# UnknownSchematic.net
KiCad netlist of a schematic drawn in EAGLE
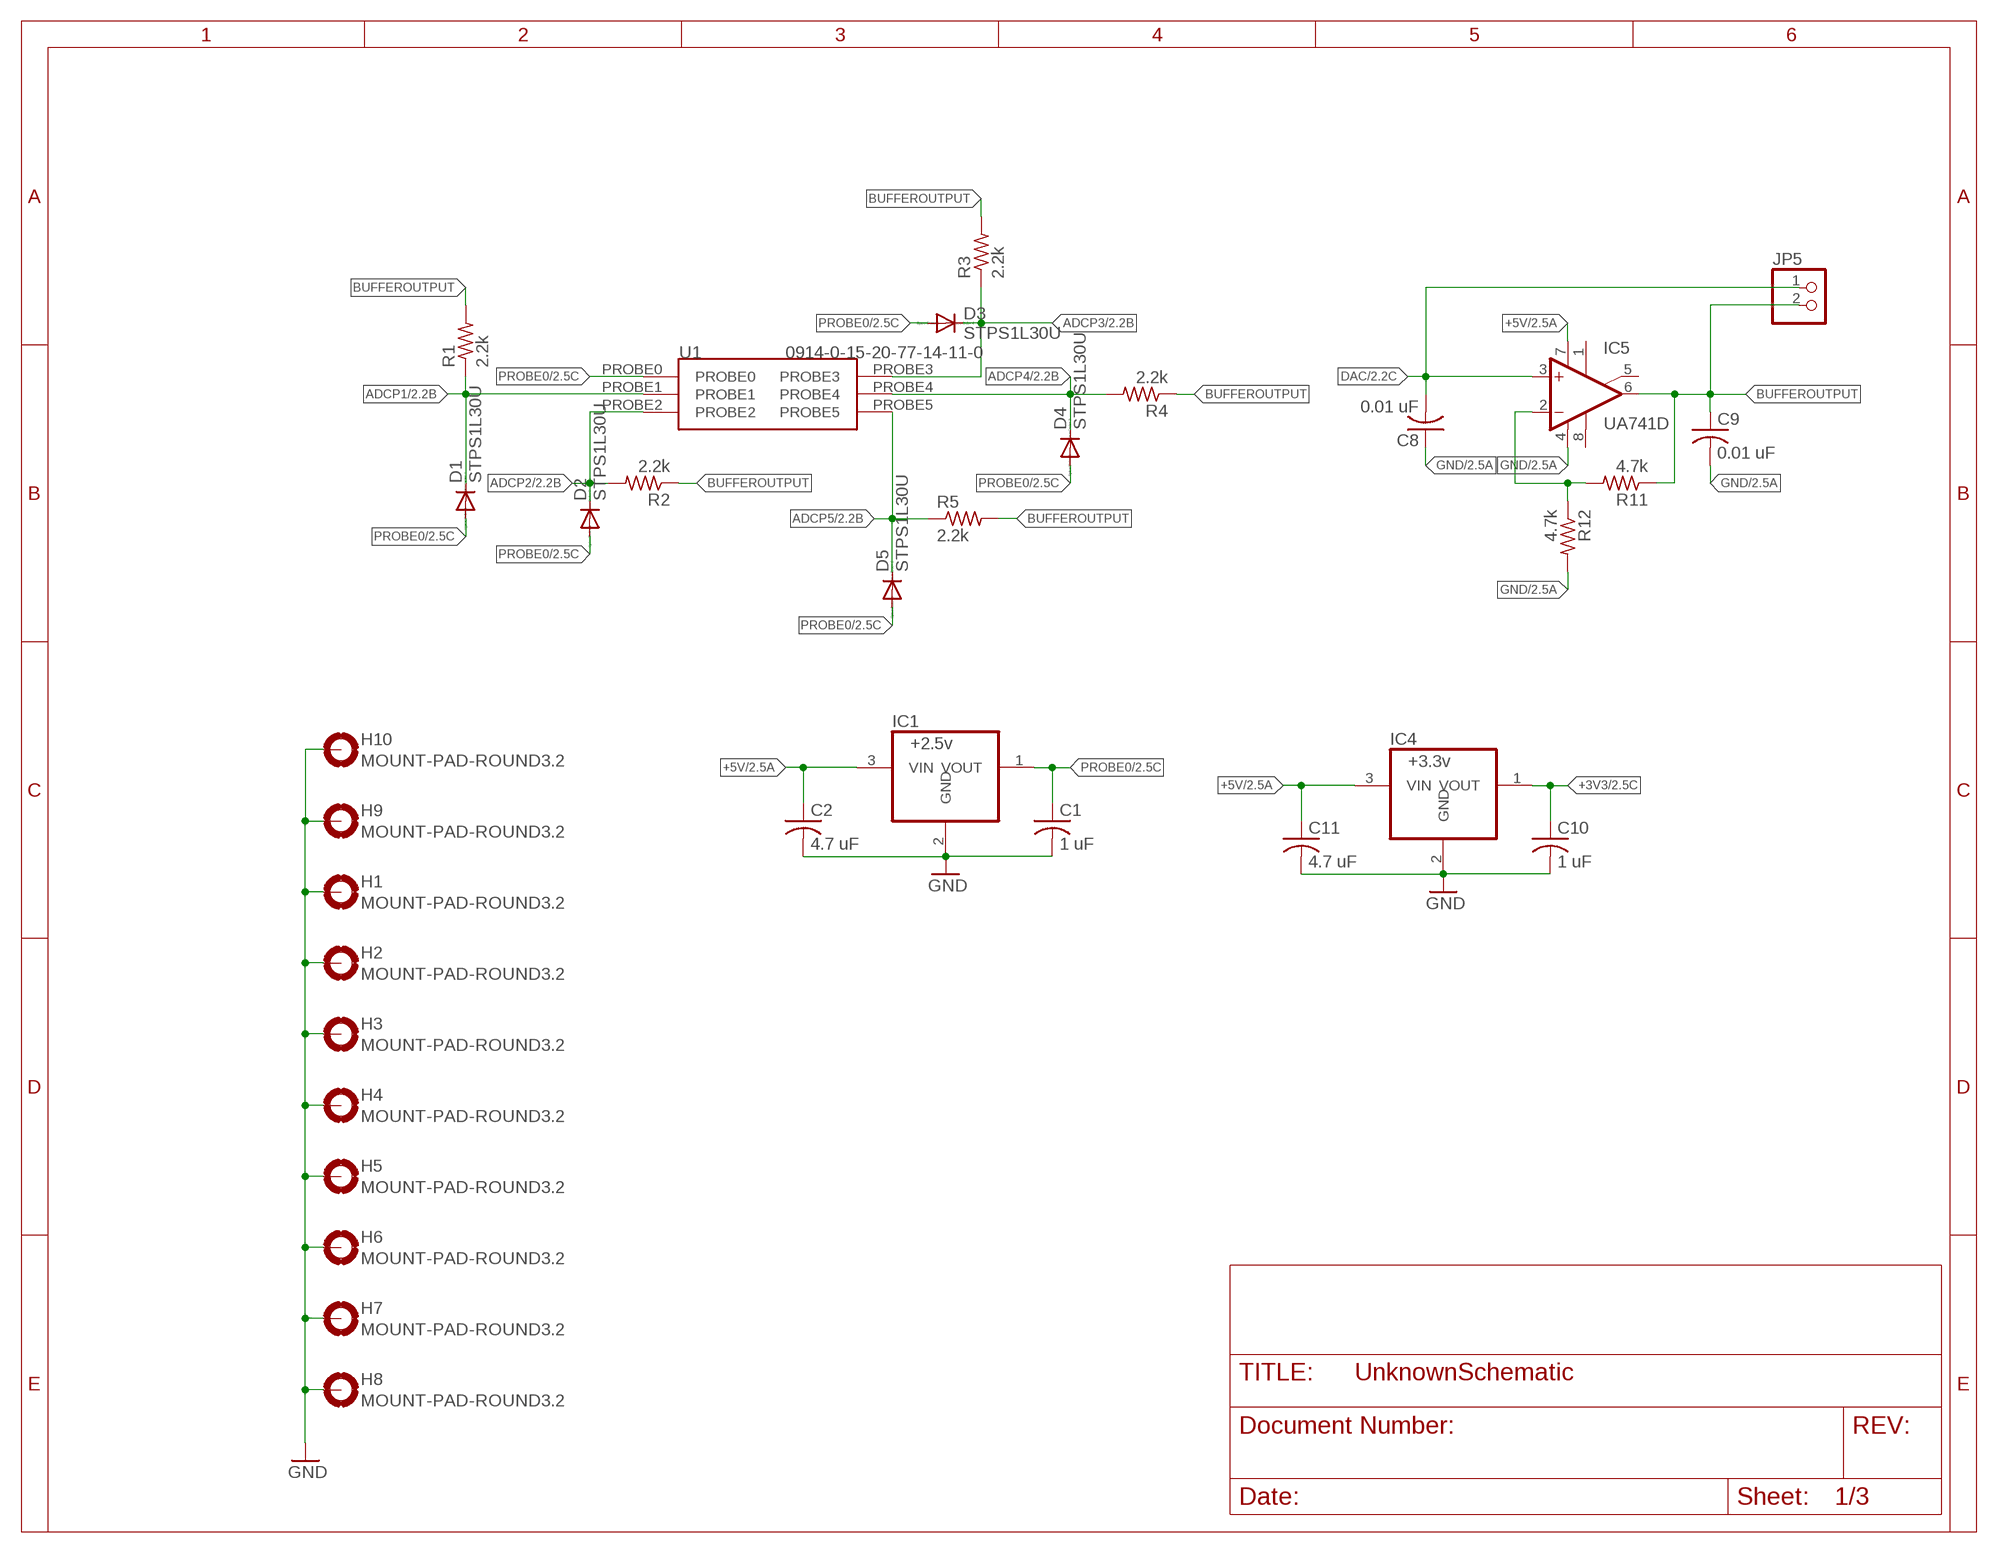
[diagram p0: schematic, sheet 1]
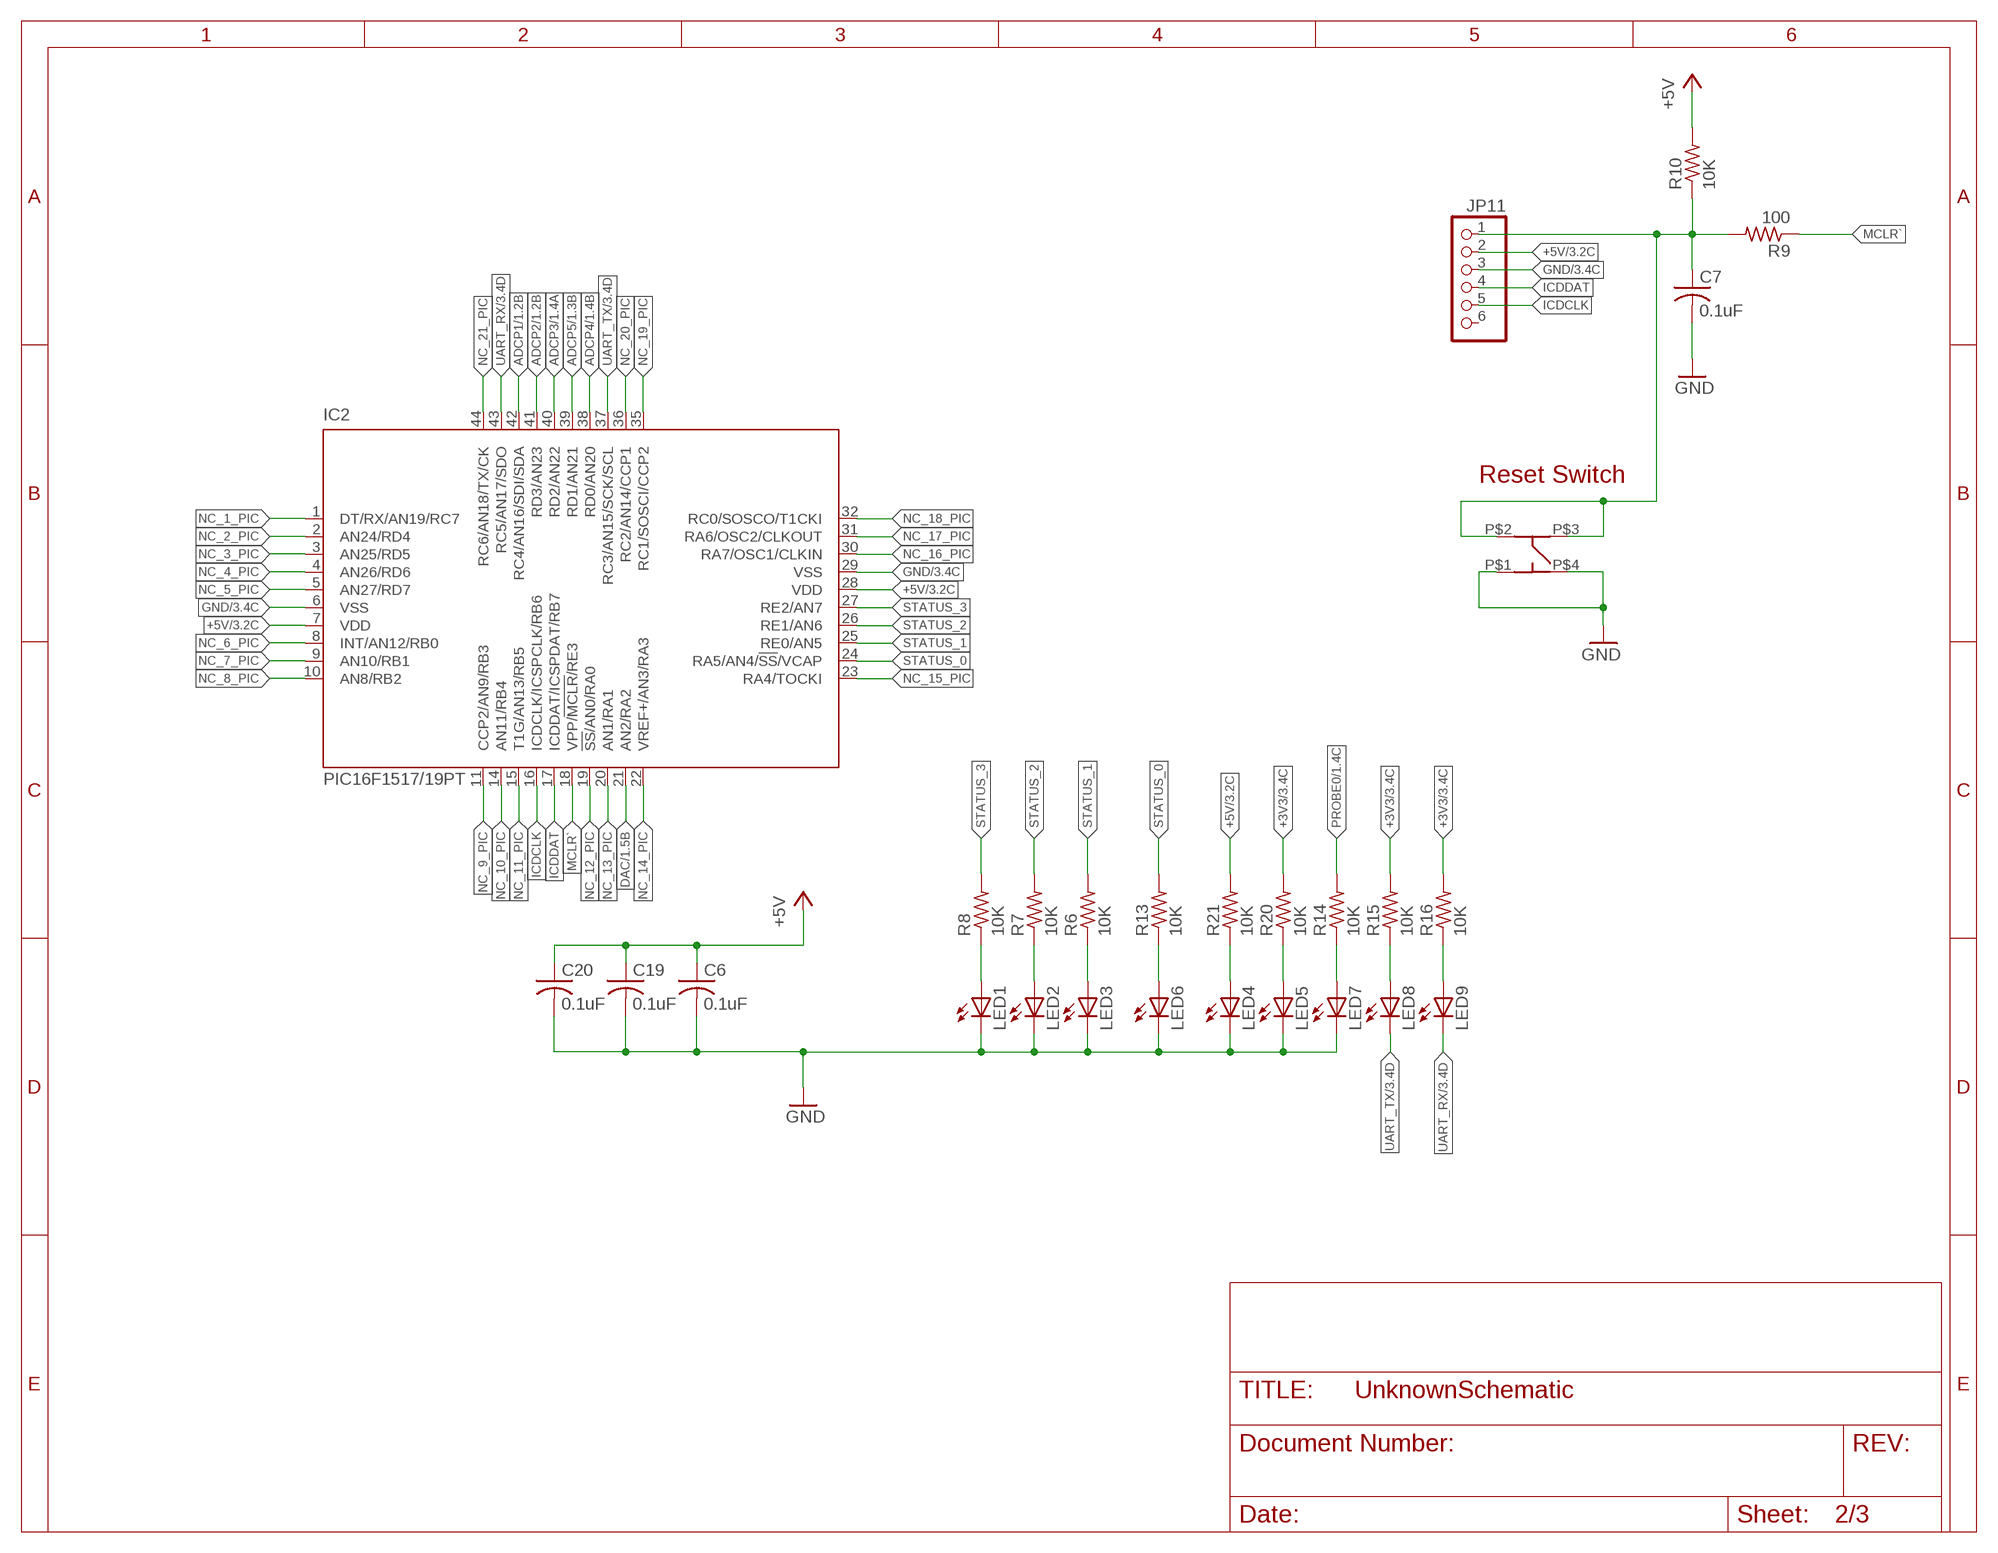
[diagram p1: schematic, sheet 2]
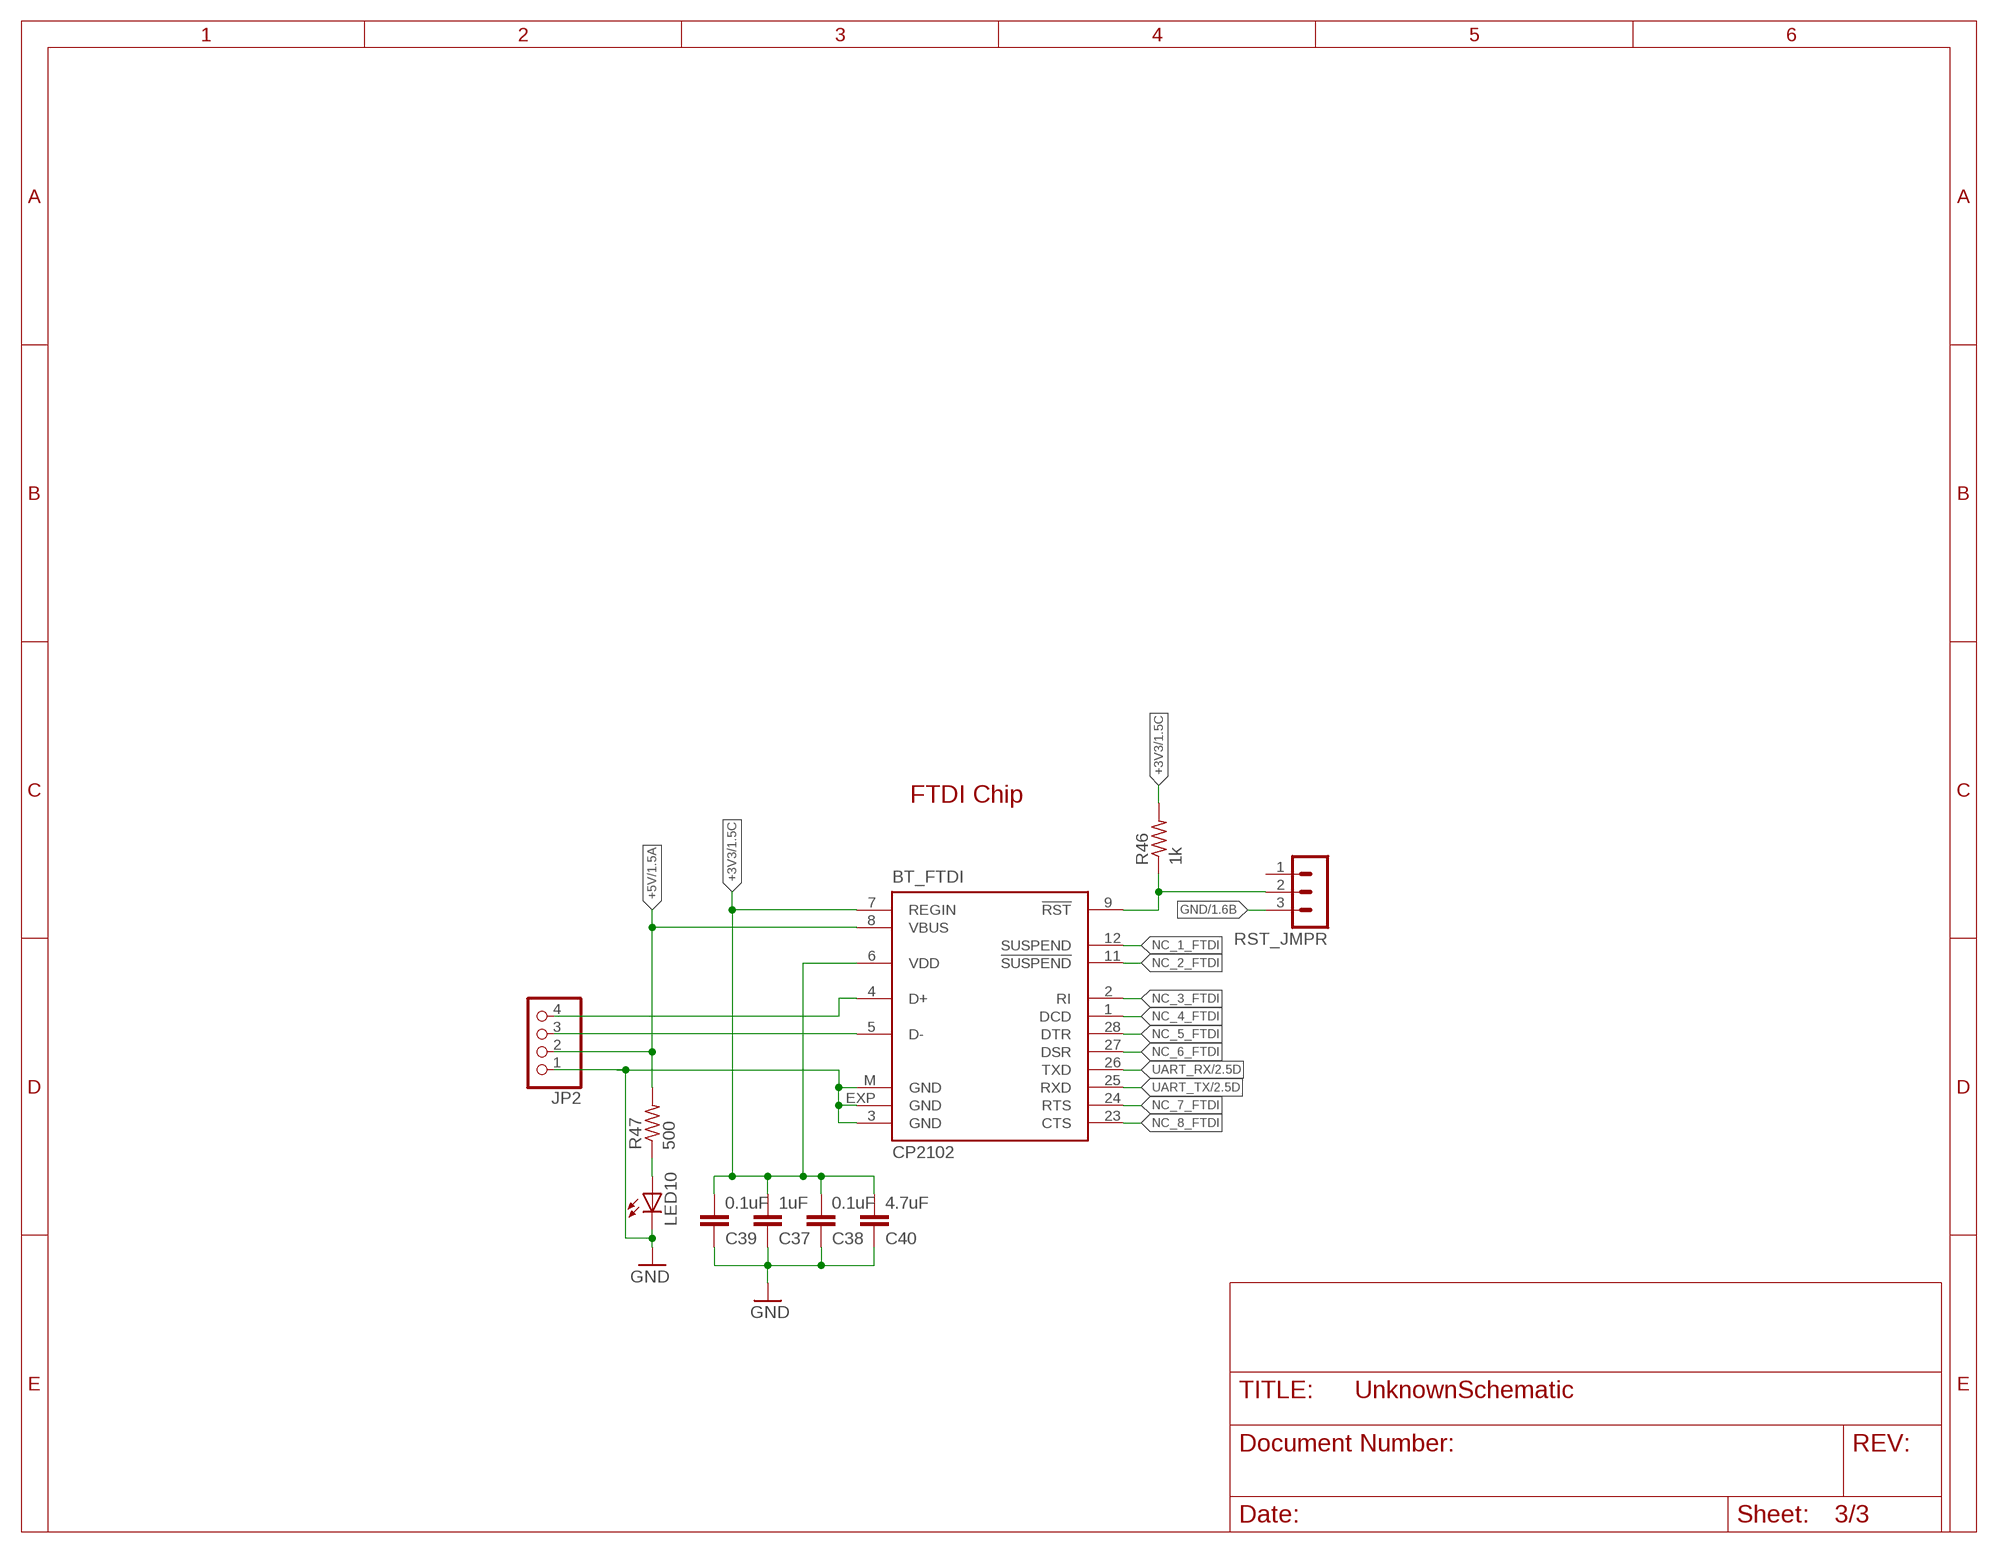
[diagram p2: schematic, sheet 3]

(export (version "E")
  (design (tool "Eeschema 10.0.6"))
  (components
    (comp (ref "BT_FTDI")
      (value "CP2102")
      (footprint "eagle-import:MLP28")
      (fields (field (name "MF") "FARNELL") (field (name "MPN") "CP2102-GM"))
      (libsource (lib "eagle-import") (part "CP2102"))
    )
    (comp (ref "C37")
      (value "1uF")
      (footprint "eagle-import:C0805")
      (libsource (lib "eagle-import") (part "C-EUC0805"))
    )
    (comp (ref "C38")
      (value "0.1uF")
      (footprint "eagle-import:C0805")
      (libsource (lib "eagle-import") (part "C-EUC0805"))
    )
    (comp (ref "C39")
      (value "0.1uF")
      (footprint "eagle-import:C0805")
      (libsource (lib "eagle-import") (part "C-EUC0805"))
    )
    (comp (ref "C40")
      (value "4.7uF")
      (footprint "eagle-import:C0805")
      (libsource (lib "eagle-import") (part "C-EUC0805"))
    )
    (comp (ref "JP2")
      (value "PINHD-1X4")
      (footprint "eagle-import:1X04")
      (libsource (lib "eagle-import") (part "PINHD-1X4"))
    )
    (comp (ref "LED10")
      (value "LEDSML0603")
      (footprint "eagle-import:SML0603")
      (libsource (lib "eagle-import") (part "LEDSML0603"))
    )
    (comp (ref "R46")
      (value "1k")
      (footprint "eagle-import:R0805")
      (libsource (lib "eagle-import") (part "resistor_R-US_R0805"))
    )
    (comp (ref "R47")
      (value "500")
      (footprint "eagle-import:R0805")
      (libsource (lib "eagle-import") (part "resistor_R-US_R0805"))
    )
    (comp (ref "RST_JMPR")
      (value "MA03-1")
      (footprint "eagle-import:MA03-1")
      (libsource (lib "eagle-import") (part "MA03-1"))
    )
    (comp (ref "C6")
      (value "0.1uF")
      (footprint "eagle-import:C0805")
      (libsource (lib "eagle-import") (part "C-USC0805"))
    )
    (comp (ref "C7")
      (value "0.1uF")
      (footprint "eagle-import:C0805")
      (libsource (lib "eagle-import") (part "C-USC0805"))
    )
    (comp (ref "C19")
      (value "0.1uF")
      (footprint "eagle-import:C0805")
      (libsource (lib "eagle-import") (part "C-USC0805"))
    )
    (comp (ref "C20")
      (value "0.1uF")
      (footprint "eagle-import:C0805")
      (libsource (lib "eagle-import") (part "C-USC0805"))
    )
    (comp (ref "IC2")
      (value "PIC16F1517/19PT")
      (footprint "eagle-import:TQFP44")
      (libsource (lib "eagle-import") (part "PIC16F1517/19PT"))
    )
    (comp (ref "JP11")
      (value "PINHD-1X6/90")
      (footprint "eagle-import:1X06_90")
      (libsource (lib "eagle-import") (part "PINHD-1X6/90"))
    )
    (comp (ref "LED1")
      (value "LEDSML0603")
      (footprint "eagle-import:SML0603")
      (libsource (lib "eagle-import") (part "LEDSML0603"))
    )
    (comp (ref "LED2")
      (value "LEDSML0603")
      (footprint "eagle-import:SML0603")
      (libsource (lib "eagle-import") (part "LEDSML0603"))
    )
    (comp (ref "LED3")
      (value "LEDSML0603")
      (footprint "eagle-import:SML0603")
      (libsource (lib "eagle-import") (part "LEDSML0603"))
    )
    (comp (ref "LED4")
      (value "LEDSML0603")
      (footprint "eagle-import:SML0603")
      (libsource (lib "eagle-import") (part "LEDSML0603"))
    )
    (comp (ref "LED5")
      (value "LEDSML0603")
      (footprint "eagle-import:SML0603")
      (libsource (lib "eagle-import") (part "LEDSML0603"))
    )
    (comp (ref "LED6")
      (value "LEDSML0603")
      (footprint "eagle-import:SML0603")
      (libsource (lib "eagle-import") (part "LEDSML0603"))
    )
    (comp (ref "LED7")
      (value "LEDSML0603")
      (footprint "eagle-import:SML0603")
      (libsource (lib "eagle-import") (part "LEDSML0603"))
    )
    (comp (ref "LED8")
      (value "LEDSML0603")
      (footprint "eagle-import:SML0603")
      (libsource (lib "eagle-import") (part "LEDSML0603"))
    )
    (comp (ref "LED9")
      (value "LEDSML0603")
      (footprint "eagle-import:SML0603")
      (libsource (lib "eagle-import") (part "LEDSML0603"))
    )
    (comp (ref "R6")
      (value "10K")
      (footprint "eagle-import:R1206")
      (libsource (lib "eagle-import") (part "R-US_R1206"))
    )
    (comp (ref "R7")
      (value "10K")
      (footprint "eagle-import:R1206")
      (libsource (lib "eagle-import") (part "R-US_R1206"))
    )
    (comp (ref "R8")
      (value "10K")
      (footprint "eagle-import:R1206")
      (libsource (lib "eagle-import") (part "R-US_R1206"))
    )
    (comp (ref "R9")
      (value "100")
      (footprint "eagle-import:R1206")
      (libsource (lib "eagle-import") (part "R-US_R1206"))
    )
    (comp (ref "R10")
      (value "10K")
      (footprint "eagle-import:R1206")
      (libsource (lib "eagle-import") (part "R-US_R1206"))
    )
    (comp (ref "R13")
      (value "10K")
      (footprint "eagle-import:R1206")
      (libsource (lib "eagle-import") (part "R-US_R1206"))
    )
    (comp (ref "R14")
      (value "10K")
      (footprint "eagle-import:R1206")
      (libsource (lib "eagle-import") (part "R-US_R1206"))
    )
    (comp (ref "R15")
      (value "10K")
      (footprint "eagle-import:R1206")
      (libsource (lib "eagle-import") (part "R-US_R1206"))
    )
    (comp (ref "R16")
      (value "10K")
      (footprint "eagle-import:R1206")
      (libsource (lib "eagle-import") (part "R-US_R1206"))
    )
    (comp (ref "R20")
      (value "10K")
      (footprint "eagle-import:R1206")
      (libsource (lib "eagle-import") (part "R-US_R1206"))
    )
    (comp (ref "R21")
      (value "10K")
      (footprint "eagle-import:R1206")
      (libsource (lib "eagle-import") (part "R-US_R1206"))
    )
    (comp (ref "TOUCH_RESET")
      (value "RESET")
      (footprint "eagle-import:MC32882_FINAL")
      (libsource (lib "eagle-import") (part "MC32882_SW"))
    )
    (comp (ref "C1")
      (value "1 uF")
      (footprint "eagle-import:C0805")
      (libsource (lib "eagle-import") (part "C-USC0805"))
    )
    (comp (ref "C2")
      (value "4.7 uF")
      (footprint "eagle-import:C0805")
      (libsource (lib "eagle-import") (part "C-USC0805"))
    )
    (comp (ref "C8")
      (value "0.01 uF")
      (footprint "eagle-import:C0805")
      (libsource (lib "eagle-import") (part "C-USC0805"))
    )
    (comp (ref "C9")
      (value "0.01 uF")
      (footprint "eagle-import:C0805")
      (libsource (lib "eagle-import") (part "C-USC0805"))
    )
    (comp (ref "C10")
      (value "1 uF")
      (footprint "eagle-import:C0805")
      (libsource (lib "eagle-import") (part "C-USC0805"))
    )
    (comp (ref "C11")
      (value "4.7 uF")
      (footprint "eagle-import:C0805")
      (libsource (lib "eagle-import") (part "C-USC0805"))
    )
    (comp (ref "D1")
      (value "STPS1L30U")
      (footprint "eagle-import:DO214AA")
      (libsource (lib "eagle-import") (part "DIODE-DO214AA"))
    )
    (comp (ref "D2")
      (value "STPS1L30U")
      (footprint "eagle-import:DO214AA")
      (libsource (lib "eagle-import") (part "DIODE-DO214AA"))
    )
    (comp (ref "D3")
      (value "STPS1L30U")
      (footprint "eagle-import:DO214AA")
      (libsource (lib "eagle-import") (part "DIODE-DO214AA"))
    )
    (comp (ref "D4")
      (value "STPS1L30U")
      (footprint "eagle-import:DO214AA")
      (libsource (lib "eagle-import") (part "DIODE-DO214AA"))
    )
    (comp (ref "D5")
      (value "STPS1L30U")
      (footprint "eagle-import:DO214AA")
      (libsource (lib "eagle-import") (part "DIODE-DO214AA"))
    )
    (comp (ref "H1")
      (value "MOUNT-PAD-ROUND3.2")
      (footprint "eagle-import:3,2-PAD")
      (libsource (lib "eagle-import") (part "MOUNT-PAD-ROUND3.2"))
    )
    (comp (ref "H2")
      (value "MOUNT-PAD-ROUND3.2")
      (footprint "eagle-import:3,2-PAD")
      (libsource (lib "eagle-import") (part "MOUNT-PAD-ROUND3.2"))
    )
    (comp (ref "H3")
      (value "MOUNT-PAD-ROUND3.2")
      (footprint "eagle-import:3,2-PAD")
      (libsource (lib "eagle-import") (part "MOUNT-PAD-ROUND3.2"))
    )
    (comp (ref "H4")
      (value "MOUNT-PAD-ROUND3.2")
      (footprint "eagle-import:3,2-PAD")
      (libsource (lib "eagle-import") (part "MOUNT-PAD-ROUND3.2"))
    )
    (comp (ref "H5")
      (value "MOUNT-PAD-ROUND3.2")
      (footprint "eagle-import:3,2-PAD")
      (libsource (lib "eagle-import") (part "MOUNT-PAD-ROUND3.2"))
    )
    (comp (ref "H6")
      (value "MOUNT-PAD-ROUND3.2")
      (footprint "eagle-import:3,2-PAD")
      (libsource (lib "eagle-import") (part "MOUNT-PAD-ROUND3.2"))
    )
    (comp (ref "H7")
      (value "MOUNT-PAD-ROUND3.2")
      (footprint "eagle-import:3,2-PAD")
      (libsource (lib "eagle-import") (part "MOUNT-PAD-ROUND3.2"))
    )
    (comp (ref "H8")
      (value "MOUNT-PAD-ROUND3.2")
      (footprint "eagle-import:3,2-PAD")
      (libsource (lib "eagle-import") (part "MOUNT-PAD-ROUND3.2"))
    )
    (comp (ref "H9")
      (value "MOUNT-PAD-ROUND3.2")
      (footprint "eagle-import:3,2-PAD")
      (libsource (lib "eagle-import") (part "MOUNT-PAD-ROUND3.2"))
    )
    (comp (ref "H10")
      (value "MOUNT-PAD-ROUND3.2")
      (footprint "eagle-import:3,2-PAD")
      (libsource (lib "eagle-import") (part "MOUNT-PAD-ROUND3.2"))
    )
    (comp (ref "IC1")
      (value "+2.5v")
      (footprint "eagle-import:SOT223")
      (fields (field (name "MPN") "REG1118-2.85/2K5G4"))
      (libsource (lib "eagle-import") (part "REG1118"))
    )
    (comp (ref "IC4")
      (value "+3.3v")
      (footprint "eagle-import:SOT223")
      (fields (field (name "MPN") "REG1118-2.85/2K5G4"))
      (libsource (lib "eagle-import") (part "REG1118"))
    )
    (comp (ref "IC5")
      (value "UA741D")
      (footprint "eagle-import:SO08")
      (libsource (lib "eagle-import") (part "741DUA"))
    )
    (comp (ref "JP5")
      (value "PINHD-1X2")
      (footprint "eagle-import:1X02")
      (libsource (lib "eagle-import") (part "PINHD-1X2"))
    )
    (comp (ref "R1")
      (value "2.2k")
      (footprint "eagle-import:R0805")
      (libsource (lib "eagle-import") (part "R-US_R0805"))
    )
    (comp (ref "R2")
      (value "2.2k")
      (footprint "eagle-import:R0805")
      (libsource (lib "eagle-import") (part "R-US_R0805"))
    )
    (comp (ref "R3")
      (value "2.2k")
      (footprint "eagle-import:R0805")
      (libsource (lib "eagle-import") (part "R-US_R0805"))
    )
    (comp (ref "R4")
      (value "2.2k")
      (footprint "eagle-import:R0805")
      (libsource (lib "eagle-import") (part "R-US_R0805"))
    )
    (comp (ref "R5")
      (value "2.2k")
      (footprint "eagle-import:R0805")
      (libsource (lib "eagle-import") (part "R-US_R0805"))
    )
    (comp (ref "R11")
      (value "4.7k")
      (footprint "eagle-import:R0805")
      (libsource (lib "eagle-import") (part "R-US_R0805"))
    )
    (comp (ref "R12")
      (value "4.7k")
      (footprint "eagle-import:R0805")
      (libsource (lib "eagle-import") (part "R-US_R0805"))
    )
    (comp (ref "U1")
      (value "0914-0-15-20-77-14-11-0")
      (footprint "eagle-import:HOLE")
      (libsource (lib "eagle-import") (part "STAGE1PROBEMOUNT"))
    )
  )
  (nets
    (net (code "1") (name "+3V3") (class "Default")
      (node (ref "BT_FTDI") (pin "6") (pinfunction "VDD_6") (pintype "power_in"))
      (node (ref "BT_FTDI") (pin "7") (pinfunction "REGIN_7") (pintype "passive"))
      (node (ref "C10") (pin "1") (pinfunction "1_1") (pintype "passive"))
      (node (ref "C37") (pin "2") (pinfunction "2_2") (pintype "passive"))
      (node (ref "C38") (pin "2") (pinfunction "2_2") (pintype "passive"))
      (node (ref "C39") (pin "2") (pinfunction "2_2") (pintype "passive"))
      (node (ref "C40") (pin "2") (pinfunction "2_2") (pintype "passive"))
      (node (ref "IC4") (pin "1") (pinfunction "VOUT_1") (pintype "output"))
      (node (ref "R15") (pin "2") (pinfunction "2_2") (pintype "passive"))
      (node (ref "R16") (pin "2") (pinfunction "2_2") (pintype "passive"))
      (node (ref "R20") (pin "2") (pinfunction "2_2") (pintype "passive"))
      (node (ref "R46") (pin "2") (pinfunction "2_2") (pintype "passive"))
    )
    (net (code "2") (name "+5V") (class "Default")
      (node (ref "BT_FTDI") (pin "8") (pinfunction "VBUS_8") (pintype "input"))
      (node (ref "C11") (pin "1") (pinfunction "1_1") (pintype "passive"))
      (node (ref "C19") (pin "1") (pinfunction "1_1") (pintype "passive"))
      (node (ref "C2") (pin "1") (pinfunction "1_1") (pintype "passive"))
      (node (ref "C20") (pin "1") (pinfunction "1_1") (pintype "passive"))
      (node (ref "C6") (pin "1") (pinfunction "1_1") (pintype "passive"))
      (node (ref "IC1") (pin "3") (pinfunction "VIN_3") (pintype "input"))
      (node (ref "IC2") (pin "28") (pinfunction "VDD_28") (pintype "power_in"))
      (node (ref "IC2") (pin "7") (pinfunction "VDD_7") (pintype "power_in"))
      (node (ref "IC4") (pin "3") (pinfunction "VIN_3") (pintype "input"))
      (node (ref "IC5") (pin "7") (pinfunction "V+_7") (pintype "power_in"))
      (node (ref "JP11") (pin "2") (pinfunction "2_2") (pintype "passive"))
      (node (ref "JP2") (pin "2") (pinfunction "2_2") (pintype "passive"))
      (node (ref "R10") (pin "2") (pinfunction "2_2") (pintype "passive"))
      (node (ref "R21") (pin "2") (pinfunction "2_2") (pintype "passive"))
      (node (ref "R47") (pin "2") (pinfunction "2_2") (pintype "passive"))
    )
    (net (code "3") (name "ADCP1") (class "Default")
      (node (ref "D1") (pin "C") (pinfunction "C_C") (pintype "passive"))
      (node (ref "IC2") (pin "42") (pinfunction "RC4/AN16/SDI/SDA_42") (pintype "bidirectional"))
      (node (ref "R1") (pin "1") (pinfunction "1_1") (pintype "passive"))
      (node (ref "U1") (pin "PROBE1") (pinfunction "PROBE1_PROBE1") (pintype "bidirectional"))
    )
    (net (code "4") (name "ADCP2") (class "Default")
      (node (ref "D2") (pin "C") (pinfunction "C_C") (pintype "passive"))
      (node (ref "IC2") (pin "41") (pinfunction "RD3/AN23_41") (pintype "bidirectional"))
      (node (ref "R2") (pin "2") (pinfunction "2_2") (pintype "passive"))
      (node (ref "U1") (pin "PROBE2") (pinfunction "PROBE2_PROBE2") (pintype "bidirectional"))
    )
    (net (code "5") (name "ADCP3") (class "Default")
      (node (ref "D3") (pin "C") (pinfunction "C_C") (pintype "passive"))
      (node (ref "IC2") (pin "40") (pinfunction "RD2/AN22_40") (pintype "bidirectional"))
      (node (ref "R3") (pin "1") (pinfunction "1_1") (pintype "passive"))
      (node (ref "U1") (pin "PROBE3") (pinfunction "PROBE3_PROBE3") (pintype "bidirectional"))
    )
    (net (code "6") (name "ADCP4") (class "Default")
      (node (ref "D4") (pin "C") (pinfunction "C_C") (pintype "passive"))
      (node (ref "IC2") (pin "38") (pinfunction "RD0/AN20_38") (pintype "bidirectional"))
      (node (ref "R4") (pin "2") (pinfunction "2_2") (pintype "passive"))
      (node (ref "U1") (pin "PROBE4") (pinfunction "PROBE4_PROBE4") (pintype "bidirectional"))
    )
    (net (code "7") (name "ADCP5") (class "Default")
      (node (ref "D5") (pin "C") (pinfunction "C_C") (pintype "passive"))
      (node (ref "IC2") (pin "39") (pinfunction "RD1/AN21_39") (pintype "bidirectional"))
      (node (ref "R5") (pin "1") (pinfunction "1_1") (pintype "passive"))
      (node (ref "U1") (pin "PROBE5") (pinfunction "PROBE5_PROBE5") (pintype "bidirectional"))
    )
    (net (code "8") (name "BUFFEROUTPUT") (class "Default")
      (node (ref "C9") (pin "1") (pinfunction "1_1") (pintype "passive"))
      (node (ref "IC5") (pin "6") (pinfunction "OUT_6") (pintype "output"))
      (node (ref "JP5") (pin "2") (pinfunction "2_2") (pintype "passive"))
      (node (ref "R1") (pin "2") (pinfunction "2_2") (pintype "passive"))
      (node (ref "R11") (pin "1") (pinfunction "1_1") (pintype "passive"))
      (node (ref "R2") (pin "1") (pinfunction "1_1") (pintype "passive"))
      (node (ref "R3") (pin "2") (pinfunction "2_2") (pintype "passive"))
      (node (ref "R4") (pin "1") (pinfunction "1_1") (pintype "passive"))
      (node (ref "R5") (pin "2") (pinfunction "2_2") (pintype "passive"))
    )
    (net (code "9") (name "DAC") (class "Default")
      (node (ref "C8") (pin "2") (pinfunction "2_2") (pintype "passive"))
      (node (ref "IC2") (pin "21") (pinfunction "AN2/RA2_21") (pintype "bidirectional"))
      (node (ref "IC5") (pin "3") (pinfunction "+IN_3") (pintype "input"))
      (node (ref "JP5") (pin "1") (pinfunction "1_1") (pintype "passive"))
    )
    (net (code "10") (name "GND") (class "Default")
      (node (ref "BT_FTDI") (pin "3") (pinfunction "GND_3") (pintype "power_in"))
      (node (ref "BT_FTDI") (pin "EXP") (pinfunction "GND_EXP") (pintype "power_in"))
      (node (ref "BT_FTDI") (pin "M") (pinfunction "GND_M") (pintype "power_in"))
      (node (ref "C1") (pin "2") (pinfunction "2_2") (pintype "passive"))
      (node (ref "C10") (pin "2") (pinfunction "2_2") (pintype "passive"))
      (node (ref "C11") (pin "2") (pinfunction "2_2") (pintype "passive"))
      (node (ref "C19") (pin "2") (pinfunction "2_2") (pintype "passive"))
      (node (ref "C2") (pin "2") (pinfunction "2_2") (pintype "passive"))
      (node (ref "C20") (pin "2") (pinfunction "2_2") (pintype "passive"))
      (node (ref "C37") (pin "1") (pinfunction "1_1") (pintype "passive"))
      (node (ref "C38") (pin "1") (pinfunction "1_1") (pintype "passive"))
      (node (ref "C39") (pin "1") (pinfunction "1_1") (pintype "passive"))
      (node (ref "C40") (pin "1") (pinfunction "1_1") (pintype "passive"))
      (node (ref "C6") (pin "2") (pinfunction "2_2") (pintype "passive"))
      (node (ref "C7") (pin "2") (pinfunction "2_2") (pintype "passive"))
      (node (ref "C8") (pin "1") (pinfunction "1_1") (pintype "passive"))
      (node (ref "C9") (pin "2") (pinfunction "2_2") (pintype "passive"))
      (node (ref "H1") (pin "B3,2") (pinfunction "MOUNT_B3,2") (pintype "passive"))
      (node (ref "H10") (pin "B3,2") (pinfunction "MOUNT_B3,2") (pintype "passive"))
      (node (ref "H2") (pin "B3,2") (pinfunction "MOUNT_B3,2") (pintype "passive"))
      (node (ref "H3") (pin "B3,2") (pinfunction "MOUNT_B3,2") (pintype "passive"))
      (node (ref "H4") (pin "B3,2") (pinfunction "MOUNT_B3,2") (pintype "passive"))
      (node (ref "H5") (pin "B3,2") (pinfunction "MOUNT_B3,2") (pintype "passive"))
      (node (ref "H6") (pin "B3,2") (pinfunction "MOUNT_B3,2") (pintype "passive"))
      (node (ref "H7") (pin "B3,2") (pinfunction "MOUNT_B3,2") (pintype "passive"))
      (node (ref "H8") (pin "B3,2") (pinfunction "MOUNT_B3,2") (pintype "passive"))
      (node (ref "H9") (pin "B3,2") (pinfunction "MOUNT_B3,2") (pintype "passive"))
      (node (ref "IC1") (pin "2") (pinfunction "GND_2") (pintype "power_in"))
      (node (ref "IC2") (pin "29") (pinfunction "VSS_29") (pintype "power_in"))
      (node (ref "IC2") (pin "6") (pinfunction "VSS_6") (pintype "power_in"))
      (node (ref "IC4") (pin "2") (pinfunction "GND_2") (pintype "power_in"))
      (node (ref "IC5") (pin "4") (pinfunction "V-_4") (pintype "power_in"))
      (node (ref "JP11") (pin "3") (pinfunction "3_3") (pintype "passive"))
      (node (ref "JP2") (pin "1") (pinfunction "1_1") (pintype "passive"))
      (node (ref "LED1") (pin "C") (pinfunction "C_C") (pintype "passive"))
      (node (ref "LED10") (pin "C") (pinfunction "C_C") (pintype "passive"))
      (node (ref "LED2") (pin "C") (pinfunction "C_C") (pintype "passive"))
      (node (ref "LED3") (pin "C") (pinfunction "C_C") (pintype "passive"))
      (node (ref "LED4") (pin "C") (pinfunction "C_C") (pintype "passive"))
      (node (ref "LED5") (pin "C") (pinfunction "C_C") (pintype "passive"))
      (node (ref "LED6") (pin "C") (pinfunction "C_C") (pintype "passive"))
      (node (ref "LED7") (pin "C") (pinfunction "C_C") (pintype "passive"))
      (node (ref "R12") (pin "2") (pinfunction "2_2") (pintype "passive"))
      (node (ref "RST_JMPR") (pin "3") (pinfunction "3_3") (pintype "passive"))
      (node (ref "TOUCH_RESET") (pin "P$1") (pinfunction "P1_P$1") (pintype "bidirectional"))
      (node (ref "TOUCH_RESET") (pin "P$4") (pinfunction "P4_P$4") (pintype "bidirectional"))
    )
    (net (code "11") (name "ICDCLK") (class "Default")
      (node (ref "IC2") (pin "16") (pinfunction "ICDCLK/ICSPCLK/RB6_16") (pintype "bidirectional"))
      (node (ref "JP11") (pin "5") (pinfunction "5_5") (pintype "passive"))
    )
    (net (code "12") (name "ICDDAT") (class "Default")
      (node (ref "IC2") (pin "17") (pinfunction "ICDDAT/ICSPDAT/RB7_17") (pintype "bidirectional"))
      (node (ref "JP11") (pin "4") (pinfunction "4_4") (pintype "passive"))
    )
    (net (code "13") (name "MCLR`") (class "Default")
      (node (ref "IC2") (pin "18") (pinfunction "VPP/~{MCLR}/RE3_18") (pintype "input"))
      (node (ref "R9") (pin "1") (pinfunction "1_1") (pintype "passive"))
    )
    (net (code "14") (name "NC_1_FTDI") (class "Default")
      (node (ref "BT_FTDI") (pin "12") (pinfunction "SUSPEND_12") (pintype "output"))
    )
    (net (code "15") (name "NC_1_PIC") (class "Default")
      (node (ref "IC2") (pin "1") (pinfunction "DT/RX/AN19/RC7_1") (pintype "bidirectional"))
    )
    (net (code "16") (name "NC_2_FTDI") (class "Default")
      (node (ref "BT_FTDI") (pin "11") (pinfunction "~{SUSPEND}_11") (pintype "output"))
    )
    (net (code "17") (name "NC_2_PIC") (class "Default")
      (node (ref "IC2") (pin "2") (pinfunction "AN24/RD4_2") (pintype "bidirectional"))
    )
    (net (code "18") (name "NC_3_FTDI") (class "Default")
      (node (ref "BT_FTDI") (pin "2") (pinfunction "RI_2") (pintype "input"))
    )
    (net (code "19") (name "NC_3_PIC") (class "Default")
      (node (ref "IC2") (pin "3") (pinfunction "AN25/RD5_3") (pintype "bidirectional"))
    )
    (net (code "20") (name "NC_4_FTDI") (class "Default")
      (node (ref "BT_FTDI") (pin "1") (pinfunction "DCD_1") (pintype "input"))
    )
    (net (code "21") (name "NC_4_PIC") (class "Default")
      (node (ref "IC2") (pin "4") (pinfunction "AN26/RD6_4") (pintype "bidirectional"))
    )
    (net (code "22") (name "NC_5_FTDI") (class "Default")
      (node (ref "BT_FTDI") (pin "28") (pinfunction "DTR_28") (pintype "output"))
    )
    (net (code "23") (name "NC_5_PIC") (class "Default")
      (node (ref "IC2") (pin "5") (pinfunction "AN27/RD7_5") (pintype "bidirectional"))
    )
    (net (code "24") (name "NC_6_FTDI") (class "Default")
      (node (ref "BT_FTDI") (pin "27") (pinfunction "DSR_27") (pintype "input"))
    )
    (net (code "25") (name "NC_6_PIC") (class "Default")
      (node (ref "IC2") (pin "8") (pinfunction "INT/AN12/RB0_8") (pintype "bidirectional"))
    )
    (net (code "26") (name "NC_7_FTDI") (class "Default")
      (node (ref "BT_FTDI") (pin "24") (pinfunction "RTS_24") (pintype "output"))
    )
    (net (code "27") (name "NC_7_PIC") (class "Default")
      (node (ref "IC2") (pin "9") (pinfunction "AN10/RB1_9") (pintype "bidirectional"))
    )
    (net (code "28") (name "NC_8_FTDI") (class "Default")
      (node (ref "BT_FTDI") (pin "23") (pinfunction "CTS_23") (pintype "input"))
    )
    (net (code "29") (name "NC_8_PIC") (class "Default")
      (node (ref "IC2") (pin "10") (pinfunction "AN8/RB2_10") (pintype "bidirectional"))
    )
    (net (code "30") (name "NC_9_PIC") (class "Default")
      (node (ref "IC2") (pin "11") (pinfunction "CCP2/AN9/RB3_11") (pintype "bidirectional"))
    )
    (net (code "31") (name "NC_10_PIC") (class "Default")
      (node (ref "IC2") (pin "14") (pinfunction "AN11/RB4_14") (pintype "bidirectional"))
    )
    (net (code "32") (name "NC_11_PIC") (class "Default")
      (node (ref "IC2") (pin "15") (pinfunction "T1G/AN13/RB5_15") (pintype "bidirectional"))
    )
    (net (code "33") (name "NC_12_PIC") (class "Default")
      (node (ref "IC2") (pin "19") (pinfunction "~{SS}/AN0/RA0_19") (pintype "bidirectional"))
    )
    (net (code "34") (name "NC_13_PIC") (class "Default")
      (node (ref "IC2") (pin "20") (pinfunction "AN1/RA1_20") (pintype "bidirectional"))
    )
    (net (code "35") (name "NC_14_PIC") (class "Default")
      (node (ref "IC2") (pin "22") (pinfunction "VREF+/AN3/RA3_22") (pintype "bidirectional"))
    )
    (net (code "36") (name "NC_15_PIC") (class "Default")
      (node (ref "IC2") (pin "23") (pinfunction "RA4/TOCKI_23") (pintype "bidirectional"))
    )
    (net (code "37") (name "NC_16_PIC") (class "Default")
      (node (ref "IC2") (pin "30") (pinfunction "RA7/OSC1/CLKIN_30") (pintype "bidirectional"))
    )
    (net (code "38") (name "NC_17_PIC") (class "Default")
      (node (ref "IC2") (pin "31") (pinfunction "RA6/OSC2/CLKOUT_31") (pintype "bidirectional"))
    )
    (net (code "39") (name "NC_18_PIC") (class "Default")
      (node (ref "IC2") (pin "32") (pinfunction "RC0/SOSCO/T1CKI_32") (pintype "bidirectional"))
    )
    (net (code "40") (name "NC_19_PIC") (class "Default")
      (node (ref "IC2") (pin "35") (pinfunction "RC1/SOSCI/CCP2_35") (pintype "bidirectional"))
    )
    (net (code "41") (name "NC_20_PIC") (class "Default")
      (node (ref "IC2") (pin "36") (pinfunction "RC2/AN14/CCP1_36") (pintype "bidirectional"))
    )
    (net (code "42") (name "NC_21_PIC") (class "Default")
      (node (ref "IC2") (pin "44") (pinfunction "RC6/AN18/TX/CK_44") (pintype "bidirectional"))
    )
    (net (code "43") (name "Net-(BT_FTDI-D+)") (class "Default")
      (node (ref "BT_FTDI") (pin "4") (pinfunction "D+_4") (pintype "bidirectional"))
      (node (ref "JP2") (pin "4") (pinfunction "4_4") (pintype "passive"))
    )
    (net (code "44") (name "Net-(BT_FTDI-D-)") (class "Default")
      (node (ref "BT_FTDI") (pin "5") (pinfunction "D-_5") (pintype "bidirectional"))
      (node (ref "JP2") (pin "3") (pinfunction "3_3") (pintype "passive"))
    )
    (net (code "45") (name "Net-(BT_FTDI-~{RST})") (class "Default")
      (node (ref "BT_FTDI") (pin "9") (pinfunction "~{RST}_9") (pintype "bidirectional"))
      (node (ref "R46") (pin "1") (pinfunction "1_1") (pintype "passive"))
      (node (ref "RST_JMPR") (pin "2") (pinfunction "2_2") (pintype "passive"))
    )
    (net (code "46") (name "Net-(IC5--IN)") (class "Default")
      (node (ref "IC5") (pin "2") (pinfunction "-IN_2") (pintype "input"))
      (node (ref "R11") (pin "2") (pinfunction "2_2") (pintype "passive"))
      (node (ref "R12") (pin "1") (pinfunction "1_1") (pintype "passive"))
    )
    (net (code "47") (name "Net-(LED1-PadA)") (class "Default")
      (node (ref "LED1") (pin "A") (pinfunction "A_A") (pintype "passive"))
      (node (ref "R8") (pin "1") (pinfunction "1_1") (pintype "passive"))
    )
    (net (code "48") (name "Net-(LED2-PadA)") (class "Default")
      (node (ref "LED2") (pin "A") (pinfunction "A_A") (pintype "passive"))
      (node (ref "R7") (pin "1") (pinfunction "1_1") (pintype "passive"))
    )
    (net (code "49") (name "Net-(LED3-PadA)") (class "Default")
      (node (ref "LED3") (pin "A") (pinfunction "A_A") (pintype "passive"))
      (node (ref "R6") (pin "1") (pinfunction "1_1") (pintype "passive"))
    )
    (net (code "50") (name "Net-(LED4-PadA)") (class "Default")
      (node (ref "LED4") (pin "A") (pinfunction "A_A") (pintype "passive"))
      (node (ref "R21") (pin "1") (pinfunction "1_1") (pintype "passive"))
    )
    (net (code "51") (name "Net-(LED5-PadA)") (class "Default")
      (node (ref "LED5") (pin "A") (pinfunction "A_A") (pintype "passive"))
      (node (ref "R20") (pin "1") (pinfunction "1_1") (pintype "passive"))
    )
    (net (code "52") (name "Net-(LED6-PadA)") (class "Default")
      (node (ref "LED6") (pin "A") (pinfunction "A_A") (pintype "passive"))
      (node (ref "R13") (pin "1") (pinfunction "1_1") (pintype "passive"))
    )
    (net (code "53") (name "Net-(LED7-PadA)") (class "Default")
      (node (ref "LED7") (pin "A") (pinfunction "A_A") (pintype "passive"))
      (node (ref "R14") (pin "1") (pinfunction "1_1") (pintype "passive"))
    )
    (net (code "54") (name "Net-(LED8-PadA)") (class "Default")
      (node (ref "LED8") (pin "A") (pinfunction "A_A") (pintype "passive"))
      (node (ref "R15") (pin "1") (pinfunction "1_1") (pintype "passive"))
    )
    (net (code "55") (name "Net-(LED9-PadA)") (class "Default")
      (node (ref "LED9") (pin "A") (pinfunction "A_A") (pintype "passive"))
      (node (ref "R16") (pin "1") (pinfunction "1_1") (pintype "passive"))
    )
    (net (code "56") (name "Net-(LED10-PadA)") (class "Default")
      (node (ref "LED10") (pin "A") (pinfunction "A_A") (pintype "passive"))
      (node (ref "R47") (pin "1") (pinfunction "1_1") (pintype "passive"))
    )
    (net (code "57") (name "Net-(TOUCH_RESET-P2)") (class "Default")
      (node (ref "C7") (pin "1") (pinfunction "1_1") (pintype "passive"))
      (node (ref "JP11") (pin "1") (pinfunction "1_1") (pintype "passive"))
      (node (ref "R10") (pin "1") (pinfunction "1_1") (pintype "passive"))
      (node (ref "R9") (pin "2") (pinfunction "2_2") (pintype "passive"))
      (node (ref "TOUCH_RESET") (pin "P$2") (pinfunction "P2_P$2") (pintype "bidirectional"))
      (node (ref "TOUCH_RESET") (pin "P$3") (pinfunction "P3_P$3") (pintype "bidirectional"))
    )
    (net (code "58") (name "PROBE0") (class "Default")
      (node (ref "C1") (pin "1") (pinfunction "1_1") (pintype "passive"))
      (node (ref "D1") (pin "A") (pinfunction "A_A") (pintype "passive"))
      (node (ref "D2") (pin "A") (pinfunction "A_A") (pintype "passive"))
      (node (ref "D3") (pin "A") (pinfunction "A_A") (pintype "passive"))
      (node (ref "D4") (pin "A") (pinfunction "A_A") (pintype "passive"))
      (node (ref "D5") (pin "A") (pinfunction "A_A") (pintype "passive"))
      (node (ref "IC1") (pin "1") (pinfunction "VOUT_1") (pintype "output"))
      (node (ref "R14") (pin "2") (pinfunction "2_2") (pintype "passive"))
      (node (ref "U1") (pin "PROBE0") (pinfunction "PROBE0_PROBE0") (pintype "bidirectional"))
    )
    (net (code "59") (name "STATUS_0") (class "Default")
      (node (ref "IC2") (pin "24") (pinfunction "RA5/AN4/~{SS}/VCAP_24") (pintype "bidirectional"))
      (node (ref "R13") (pin "2") (pinfunction "2_2") (pintype "passive"))
    )
    (net (code "60") (name "STATUS_1") (class "Default")
      (node (ref "IC2") (pin "25") (pinfunction "RE0/AN5_25") (pintype "bidirectional"))
      (node (ref "R6") (pin "2") (pinfunction "2_2") (pintype "passive"))
    )
    (net (code "61") (name "STATUS_2") (class "Default")
      (node (ref "IC2") (pin "26") (pinfunction "RE1/AN6_26") (pintype "bidirectional"))
      (node (ref "R7") (pin "2") (pinfunction "2_2") (pintype "passive"))
    )
    (net (code "62") (name "STATUS_3") (class "Default")
      (node (ref "IC2") (pin "27") (pinfunction "RE2/AN7_27") (pintype "bidirectional"))
      (node (ref "R8") (pin "2") (pinfunction "2_2") (pintype "passive"))
    )
    (net (code "63") (name "UART_RX") (class "Default")
      (node (ref "BT_FTDI") (pin "26") (pinfunction "TXD_26") (pintype "output"))
      (node (ref "IC2") (pin "43") (pinfunction "RC5/AN17/SDO_43") (pintype "bidirectional"))
      (node (ref "LED9") (pin "C") (pinfunction "C_C") (pintype "passive"))
    )
    (net (code "64") (name "UART_TX") (class "Default")
      (node (ref "BT_FTDI") (pin "25") (pinfunction "RXD_25") (pintype "input"))
      (node (ref "IC2") (pin "37") (pinfunction "RC3/AN15/SCK/SCL_37") (pintype "bidirectional"))
      (node (ref "LED8") (pin "C") (pinfunction "C_C") (pintype "passive"))
    )
    (net (code "65") (name "unconnected-(IC5-ON1-Pad1)") (class "Default")
      (node (ref "IC5") (pin "1") (pinfunction "ON1_1") (pintype "passive"))
    )
    (net (code "66") (name "unconnected-(IC5-ON2-Pad5)") (class "Default")
      (node (ref "IC5") (pin "5") (pinfunction "ON2_5") (pintype "passive"))
    )
    (net (code "67") (name "unconnected-(IC5-OPT-Pad8)") (class "Default")
      (node (ref "IC5") (pin "8") (pinfunction "OPT_8") (pintype "passive"))
    )
    (net (code "68") (name "unconnected-(JP11-Pad6)") (class "Default")
      (node (ref "JP11") (pin "6") (pinfunction "6_6") (pintype "passive"))
    )
    (net (code "69") (name "unconnected-(RST_JMPR-Pad1)") (class "Default")
      (node (ref "RST_JMPR") (pin "1") (pinfunction "1_1") (pintype "passive"))
    )
  )
)
